# sdCard.net
KiCad netlist of a schematic drawn in Altium Designer
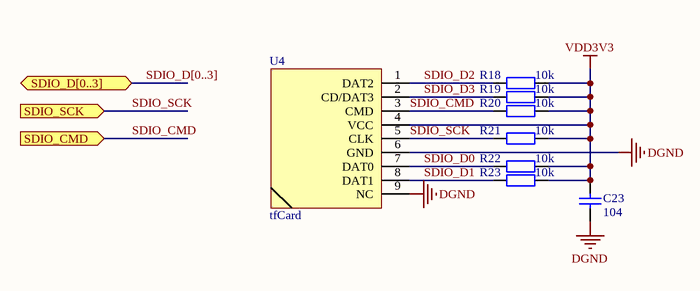
[diagram p0: sdCard.SchDoc]

(export (version "E")
  (design (tool "Eeschema 10.0.6"))
  (components
    (comp (ref "C23") (value "104") (footprint "0603_") (libsource (lib "chxxlib") (part "cap")))
    (comp (ref "R18") (value "10k") (footprint "0603_") (libsource (lib "chxxlib") (part "res")))
    (comp (ref "R19") (value "10k") (footprint "0603_") (libsource (lib "chxxlib") (part "res")))
    (comp (ref "R20") (value "10k") (footprint "0603_") (libsource (lib "chxxlib") (part "res")))
    (comp (ref "R21") (value "10k") (footprint "0603_") (libsource (lib "chxxlib") (part "res")))
    (comp (ref "R22") (value "10k") (footprint "0603_") (libsource (lib "chxxlib") (part "res")))
    (comp (ref "R23") (value "10k") (footprint "0603_") (libsource (lib "chxxlib") (part "res")))
    (comp (ref "U4") (value "tfCard") (footprint "tfCard") (libsource (lib "chxxlib") (part "tfCard")))
  )
  (nets
    (net (code "1") (name "/SDIO_CMD") (class "Default")
      (node (ref "R20") (pin "1") (pinfunction "1_1") (pintype "passive"))
      (node (ref "U4") (pin "3") (pinfunction "CMD_3") (pintype "passive"))
    )
    (net (code "2") (name "/SDIO_D0") (class "Default")
      (node (ref "R22") (pin "1") (pinfunction "1_1") (pintype "passive"))
      (node (ref "U4") (pin "7") (pinfunction "DAT0_7") (pintype "passive"))
    )
    (net (code "3") (name "/SDIO_D1") (class "Default")
      (node (ref "R23") (pin "1") (pinfunction "1_1") (pintype "passive"))
      (node (ref "U4") (pin "8") (pinfunction "DAT1_8") (pintype "passive"))
    )
    (net (code "4") (name "/SDIO_D2") (class "Default")
      (node (ref "R18") (pin "1") (pinfunction "1_1") (pintype "passive"))
      (node (ref "U4") (pin "1") (pinfunction "DAT2_1") (pintype "passive"))
    )
    (net (code "5") (name "/SDIO_D3") (class "Default")
      (node (ref "R19") (pin "1") (pinfunction "1_1") (pintype "passive"))
      (node (ref "U4") (pin "2") (pinfunction "CD/DAT3_2") (pintype "passive"))
    )
    (net (code "7") (name "/SDIO_SCK") (class "Default")
      (node (ref "R21") (pin "1") (pinfunction "1_1") (pintype "passive"))
      (node (ref "U4") (pin "5") (pinfunction "CLK_5") (pintype "passive"))
    )
    (net (code "8") (name "DGND") (class "Default")
      (node (ref "C23") (pin "1") (pinfunction "1_1") (pintype "passive"))
      (node (ref "U4") (pin "6") (pinfunction "GND_6") (pintype "passive"))
      (node (ref "U4") (pin "9") (pinfunction "NC_9") (pintype "passive"))
    )
    (net (code "9") (name "VDD3V3") (class "Default")
      (node (ref "C23") (pin "2") (pinfunction "2_2") (pintype "passive"))
      (node (ref "R18") (pin "2") (pinfunction "2_2") (pintype "passive"))
      (node (ref "R19") (pin "2") (pinfunction "2_2") (pintype "passive"))
      (node (ref "R20") (pin "2") (pinfunction "2_2") (pintype "passive"))
      (node (ref "R21") (pin "2") (pinfunction "2_2") (pintype "passive"))
      (node (ref "R22") (pin "2") (pinfunction "2_2") (pintype "passive"))
      (node (ref "R23") (pin "2") (pinfunction "2_2") (pintype "passive"))
      (node (ref "U4") (pin "4") (pinfunction "VCC_4") (pintype "passive"))
    )
  )
)
